# 18500_pack.net
KiCad netlist of a schematic drawn in EAGLE
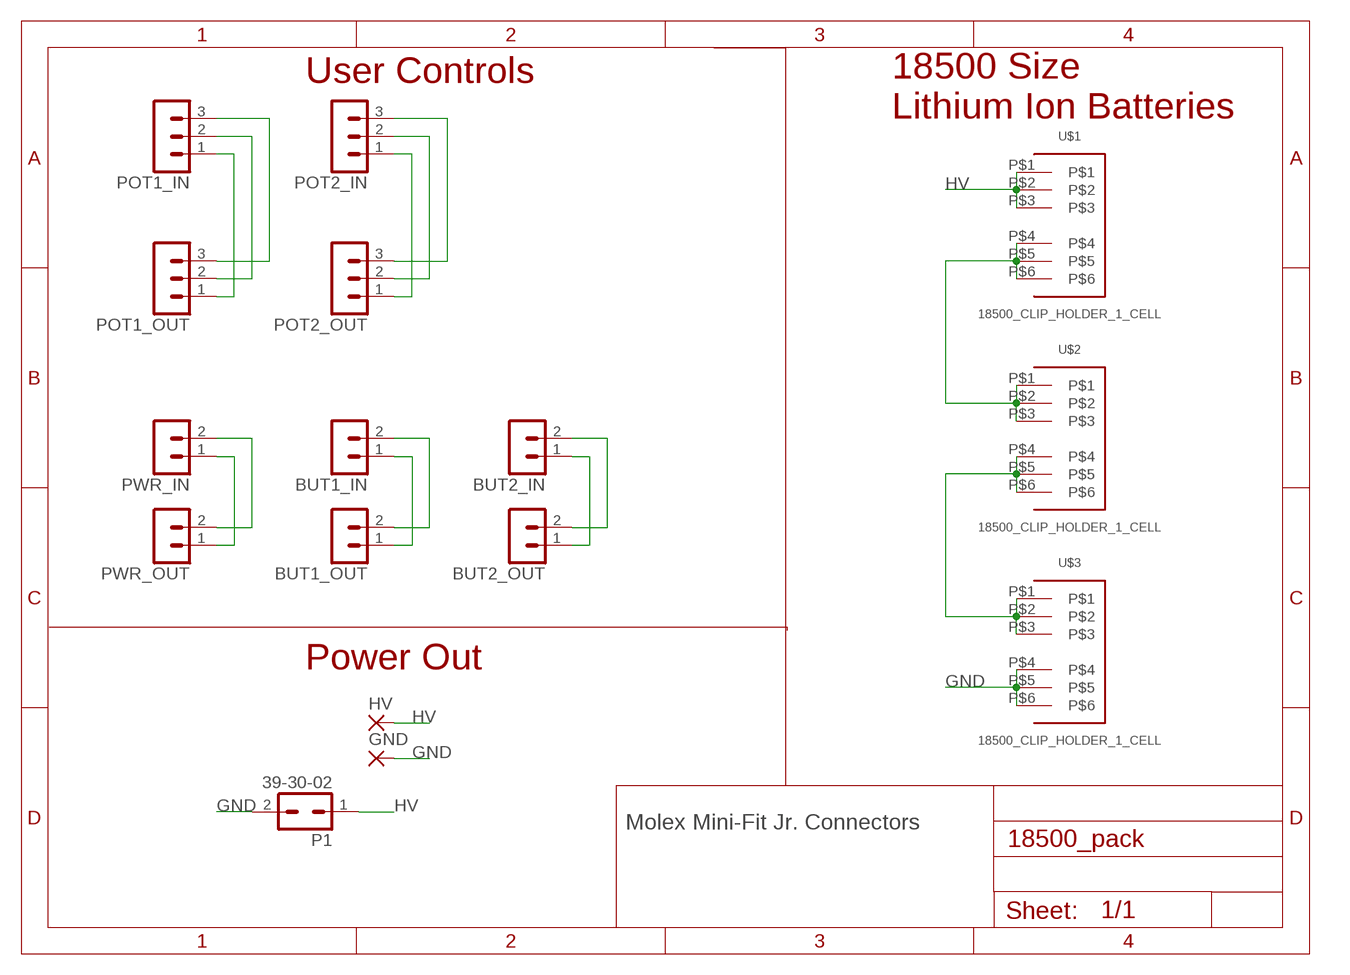
[diagram p0: schematic, sheet 1]

(export (version "E")
  (design (tool "Eeschema 10.0.6"))
  (components
    (comp (ref "BUT1_IN")
      (value "B2B-PH-K")
      (footprint "eagle-import:B2B-PH-K")
      (libsource (lib "eagle-import") (part "B2B-PH-K"))
    )
    (comp (ref "BUT1_OUT")
      (value "B2B-PH-K")
      (footprint "eagle-import:B2B-PH-K")
      (libsource (lib "eagle-import") (part "B2B-PH-K"))
    )
    (comp (ref "BUT2_IN")
      (value "B2B-PH-K")
      (footprint "eagle-import:B2B-PH-K")
      (libsource (lib "eagle-import") (part "B2B-PH-K"))
    )
    (comp (ref "BUT2_OUT")
      (value "B2B-PH-K")
      (footprint "eagle-import:B2B-PH-K")
      (libsource (lib "eagle-import") (part "B2B-PH-K"))
    )
    (comp (ref "GND")
      (value "2,54/1,1")
      (footprint "eagle-import:2,54_1,1")
      (libsource (lib "eagle-import") (part "2,54/1,1"))
    )
    (comp (ref "HV")
      (value "2,54/1,1")
      (footprint "eagle-import:2,54_1,1")
      (libsource (lib "eagle-import") (part "2,54/1,1"))
    )
    (comp (ref "P1")
      (value "39-30-02")
      (footprint "eagle-import:39-30-_02_")
      (libsource (lib "eagle-import") (part "39-30-?02?"))
    )
    (comp (ref "POT1_IN")
      (value "B3B-PH-K")
      (footprint "eagle-import:B3B-PH-K")
      (libsource (lib "eagle-import") (part "B3B-PH-K"))
    )
    (comp (ref "POT1_OUT")
      (value "B3B-PH-K")
      (footprint "eagle-import:B3B-PH-K")
      (libsource (lib "eagle-import") (part "B3B-PH-K"))
    )
    (comp (ref "POT2_IN")
      (value "B3B-PH-K")
      (footprint "eagle-import:B3B-PH-K")
      (libsource (lib "eagle-import") (part "B3B-PH-K"))
    )
    (comp (ref "POT2_OUT")
      (value "B3B-PH-K")
      (footprint "eagle-import:B3B-PH-K")
      (libsource (lib "eagle-import") (part "B3B-PH-K"))
    )
    (comp (ref "PWR_IN")
      (value "B2B-PH-K")
      (footprint "eagle-import:B2B-PH-K")
      (libsource (lib "eagle-import") (part "B2B-PH-K"))
    )
    (comp (ref "PWR_OUT")
      (value "B2B-PH-K")
      (footprint "eagle-import:B2B-PH-K")
      (libsource (lib "eagle-import") (part "B2B-PH-K"))
    )
    (comp (ref "U$1")
      (value "18500_CLIP_HOLDER_1_CELL")
      (footprint "eagle-import:3PINBATTERY_CLIP_1_CELL_18500")
      (libsource (lib "eagle-import") (part "18500_CLIP_HOLDER_1_CELL"))
    )
    (comp (ref "U$2")
      (value "18500_CLIP_HOLDER_1_CELL")
      (footprint "eagle-import:3PINBATTERY_CLIP_1_CELL_18500")
      (libsource (lib "eagle-import") (part "18500_CLIP_HOLDER_1_CELL"))
    )
    (comp (ref "U$3")
      (value "18500_CLIP_HOLDER_1_CELL")
      (footprint "eagle-import:3PINBATTERY_CLIP_1_CELL_18500")
      (libsource (lib "eagle-import") (part "18500_CLIP_HOLDER_1_CELL"))
    )
  )
  (nets
    (net (code "1") (name "/GND") (class "Default")
      (node (ref "GND") (pin "1") (pinfunction "P_1") (pintype "passive"))
      (node (ref "P1") (pin "2") (pinfunction "2_2") (pintype "passive"))
      (node (ref "U$3") (pin "P$4") (pinfunction "P$4_P$4") (pintype "bidirectional"))
      (node (ref "U$3") (pin "P$5") (pinfunction "P$5_P$5") (pintype "bidirectional"))
      (node (ref "U$3") (pin "P$6") (pinfunction "P$6_P$6") (pintype "bidirectional"))
    )
    (net (code "2") (name "/HV") (class "Default")
      (node (ref "HV") (pin "1") (pinfunction "P_1") (pintype "passive"))
      (node (ref "P1") (pin "1") (pinfunction "1_1") (pintype "passive"))
      (node (ref "U$1") (pin "P$1") (pinfunction "P$1_P$1") (pintype "bidirectional"))
      (node (ref "U$1") (pin "P$2") (pinfunction "P$2_P$2") (pintype "bidirectional"))
      (node (ref "U$1") (pin "P$3") (pinfunction "P$3_P$3") (pintype "bidirectional"))
    )
    (net (code "3") (name "Net-(BUT1_IN-Pad1)") (class "Default")
      (node (ref "BUT1_IN") (pin "1") (pinfunction "1_1") (pintype "passive"))
      (node (ref "BUT1_OUT") (pin "1") (pinfunction "1_1") (pintype "passive"))
    )
    (net (code "4") (name "Net-(BUT1_IN-Pad2)") (class "Default")
      (node (ref "BUT1_IN") (pin "2") (pinfunction "2_2") (pintype "passive"))
      (node (ref "BUT1_OUT") (pin "2") (pinfunction "2_2") (pintype "passive"))
    )
    (net (code "5") (name "Net-(BUT2_IN-Pad1)") (class "Default")
      (node (ref "BUT2_IN") (pin "1") (pinfunction "1_1") (pintype "passive"))
      (node (ref "BUT2_OUT") (pin "1") (pinfunction "1_1") (pintype "passive"))
    )
    (net (code "6") (name "Net-(BUT2_IN-Pad2)") (class "Default")
      (node (ref "BUT2_IN") (pin "2") (pinfunction "2_2") (pintype "passive"))
      (node (ref "BUT2_OUT") (pin "2") (pinfunction "2_2") (pintype "passive"))
    )
    (net (code "7") (name "Net-(POT1_IN-Pad1)") (class "Default")
      (node (ref "POT1_IN") (pin "1") (pinfunction "1_1") (pintype "passive"))
      (node (ref "POT1_OUT") (pin "1") (pinfunction "1_1") (pintype "passive"))
    )
    (net (code "8") (name "Net-(POT1_IN-Pad2)") (class "Default")
      (node (ref "POT1_IN") (pin "2") (pinfunction "2_2") (pintype "passive"))
      (node (ref "POT1_OUT") (pin "2") (pinfunction "2_2") (pintype "passive"))
    )
    (net (code "9") (name "Net-(POT1_IN-Pad3)") (class "Default")
      (node (ref "POT1_IN") (pin "3") (pinfunction "3_3") (pintype "passive"))
      (node (ref "POT1_OUT") (pin "3") (pinfunction "3_3") (pintype "passive"))
    )
    (net (code "10") (name "Net-(POT2_IN-Pad1)") (class "Default")
      (node (ref "POT2_IN") (pin "1") (pinfunction "1_1") (pintype "passive"))
      (node (ref "POT2_OUT") (pin "1") (pinfunction "1_1") (pintype "passive"))
    )
    (net (code "11") (name "Net-(POT2_IN-Pad2)") (class "Default")
      (node (ref "POT2_IN") (pin "2") (pinfunction "2_2") (pintype "passive"))
      (node (ref "POT2_OUT") (pin "2") (pinfunction "2_2") (pintype "passive"))
    )
    (net (code "12") (name "Net-(POT2_IN-Pad3)") (class "Default")
      (node (ref "POT2_IN") (pin "3") (pinfunction "3_3") (pintype "passive"))
      (node (ref "POT2_OUT") (pin "3") (pinfunction "3_3") (pintype "passive"))
    )
    (net (code "13") (name "Net-(PWR_IN-Pad1)") (class "Default")
      (node (ref "PWR_IN") (pin "1") (pinfunction "1_1") (pintype "passive"))
      (node (ref "PWR_OUT") (pin "1") (pinfunction "1_1") (pintype "passive"))
    )
    (net (code "14") (name "Net-(PWR_IN-Pad2)") (class "Default")
      (node (ref "PWR_IN") (pin "2") (pinfunction "2_2") (pintype "passive"))
      (node (ref "PWR_OUT") (pin "2") (pinfunction "2_2") (pintype "passive"))
    )
    (net (code "15") (name "Net-(U$1-PadP$4)") (class "Default")
      (node (ref "U$1") (pin "P$4") (pinfunction "P$4_P$4") (pintype "bidirectional"))
      (node (ref "U$1") (pin "P$5") (pinfunction "P$5_P$5") (pintype "bidirectional"))
      (node (ref "U$1") (pin "P$6") (pinfunction "P$6_P$6") (pintype "bidirectional"))
      (node (ref "U$2") (pin "P$1") (pinfunction "P$1_P$1") (pintype "bidirectional"))
      (node (ref "U$2") (pin "P$2") (pinfunction "P$2_P$2") (pintype "bidirectional"))
      (node (ref "U$2") (pin "P$3") (pinfunction "P$3_P$3") (pintype "bidirectional"))
    )
    (net (code "16") (name "Net-(U$2-PadP$4)") (class "Default")
      (node (ref "U$2") (pin "P$4") (pinfunction "P$4_P$4") (pintype "bidirectional"))
      (node (ref "U$2") (pin "P$5") (pinfunction "P$5_P$5") (pintype "bidirectional"))
      (node (ref "U$2") (pin "P$6") (pinfunction "P$6_P$6") (pintype "bidirectional"))
      (node (ref "U$3") (pin "P$1") (pinfunction "P$1_P$1") (pintype "bidirectional"))
      (node (ref "U$3") (pin "P$2") (pinfunction "P$2_P$2") (pintype "bidirectional"))
      (node (ref "U$3") (pin "P$3") (pinfunction "P$3_P$3") (pintype "bidirectional"))
    )
  )
)
